# Memory-Buffer.net
KiCad netlist of a schematic drawn in Altium Designer
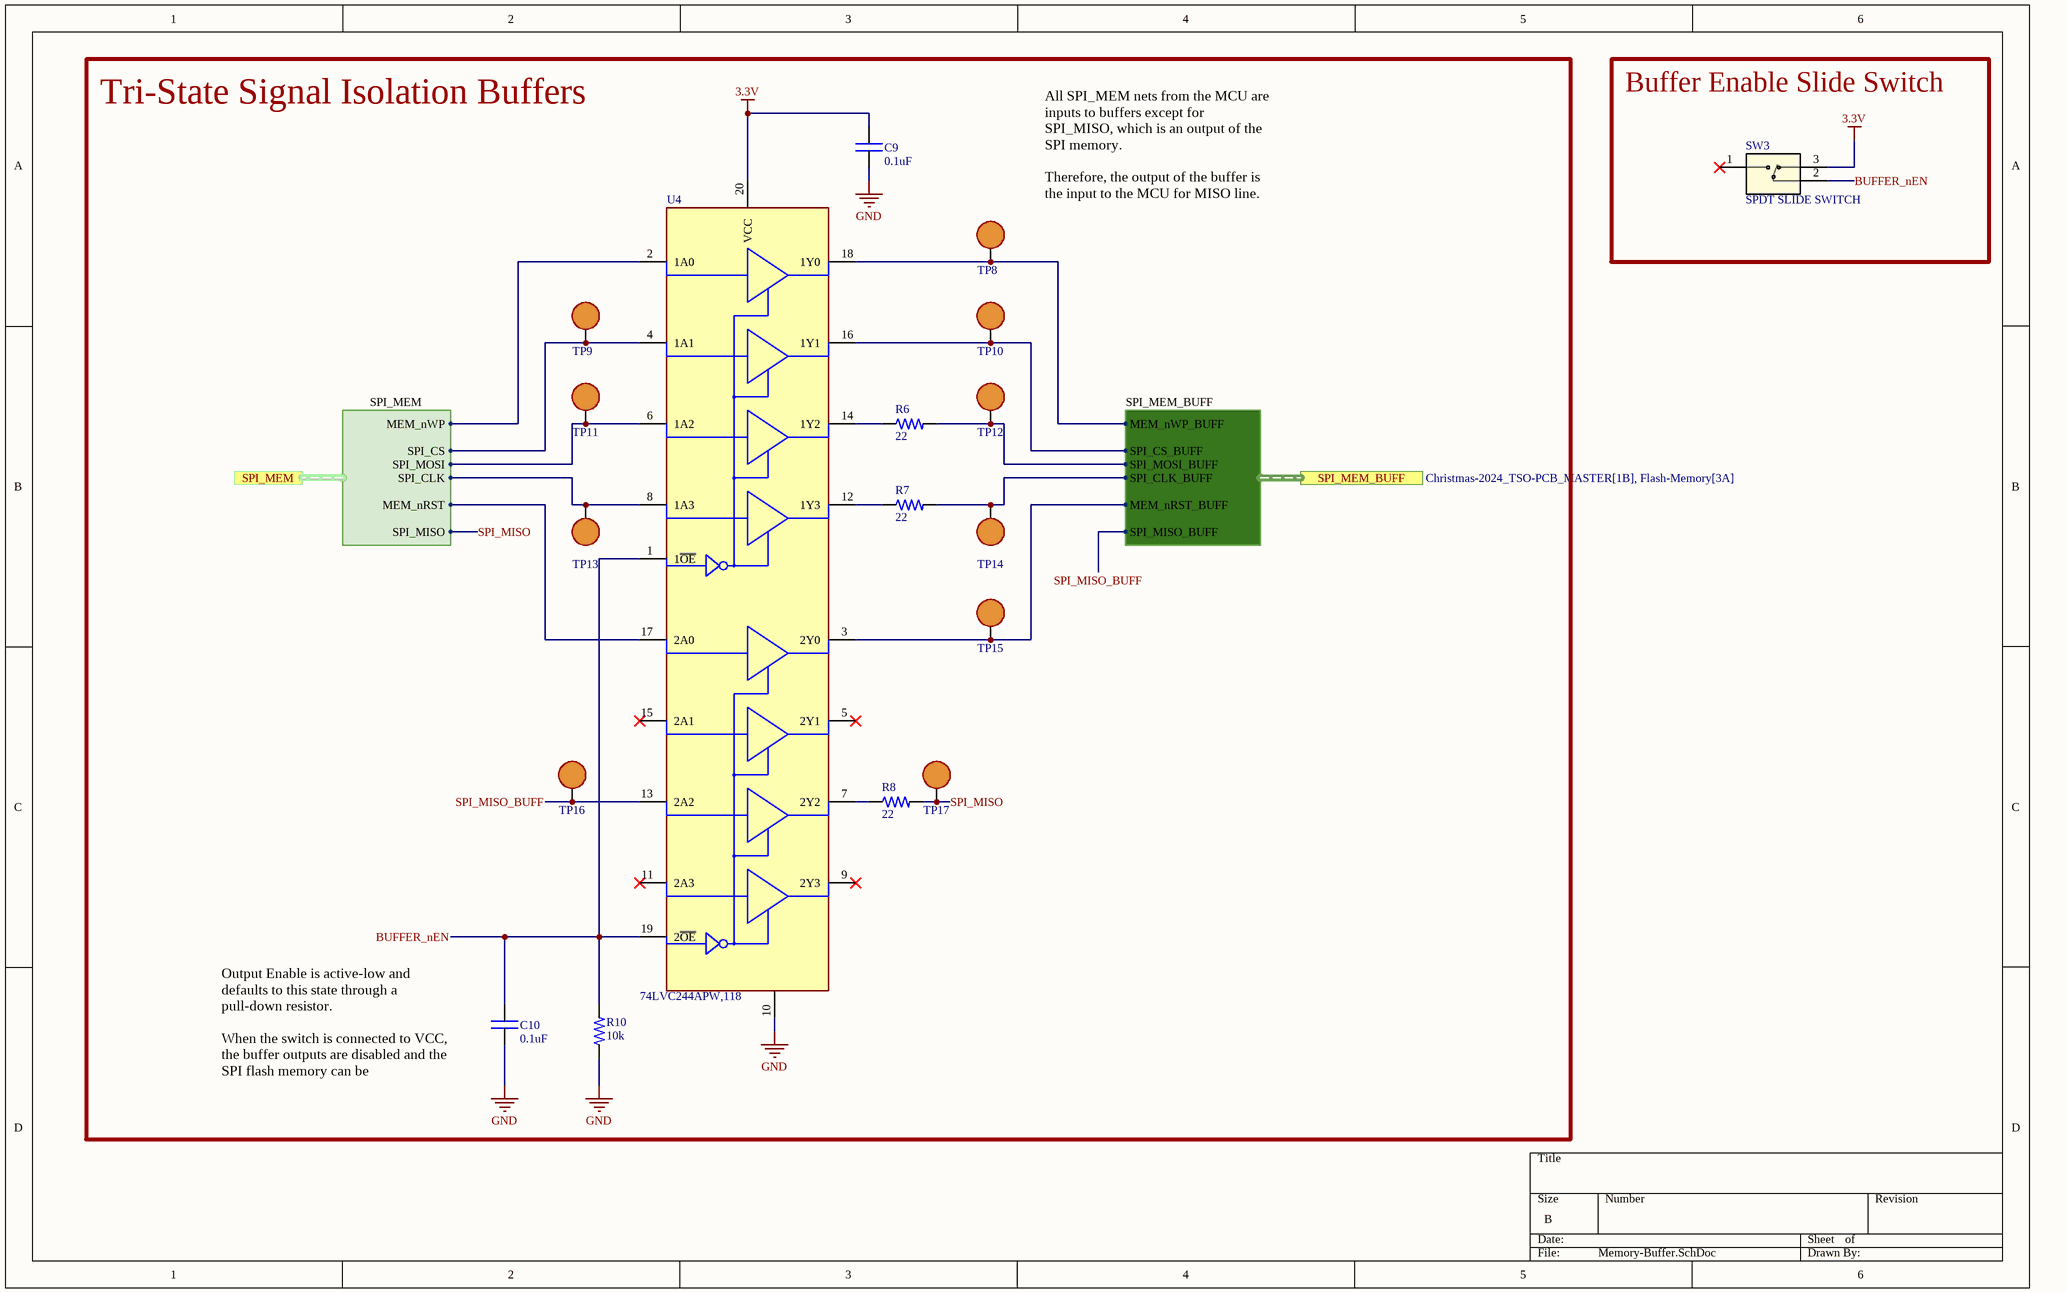
[diagram p0: Memory-Buffer.SchDoc]

(export (version "E")
  (design (tool "Eeschema 10.0.6"))
  (components
    (comp (ref "C9")
      (value "0.1uF")
      (footprint "Christmas-2024_TSO-PCB:0402C")
      (description "Capacitor")
      (fields (field (name "MFR") "Samsung") (field (name "Comment") "CAP"))
      (libsource (lib "Christmas-2024_TSO-PCB") (part "CAP"))
    )
    (comp (ref "C10")
      (value "0.1uF")
      (footprint "Christmas-2024_TSO-PCB:0402C")
      (description "Capacitor")
      (fields (field (name "MFR") "Samsung") (field (name "Comment") "CAP"))
      (libsource (lib "Christmas-2024_TSO-PCB") (part "CAP"))
    )
    (comp (ref "R6")
      (value "22")
      (footprint "Christmas-2024_TSO-PCB:0402R")
      (description "Resistor")
      (fields (field (name "MFR") "YAGEO") (field (name "Comment") "RES"))
      (libsource (lib "Christmas-2024_TSO-PCB") (part "RES"))
    )
    (comp (ref "R7")
      (value "22")
      (footprint "Christmas-2024_TSO-PCB:0402R")
      (description "Resistor")
      (fields (field (name "MFR") "YAGEO") (field (name "Comment") "RES"))
      (libsource (lib "Christmas-2024_TSO-PCB") (part "RES"))
    )
    (comp (ref "R8")
      (value "22")
      (footprint "Christmas-2024_TSO-PCB:0402R")
      (description "Resistor")
      (fields (field (name "MFR") "YAGEO") (field (name "Comment") "RES"))
      (libsource (lib "Christmas-2024_TSO-PCB") (part "RES"))
    )
    (comp (ref "R10")
      (value "10k")
      (footprint "Christmas-2024_TSO-PCB:0402R")
      (description "Resistor")
      (fields (field (name "MFR") "YAGEO") (field (name "Comment") "RES"))
      (libsource (lib "Christmas-2024_TSO-PCB") (part "RES"))
    )
    (comp (ref "SW3")
      (value "SPDT SLIDE SWITCH")
      (footprint "Christmas-2024_TSO-PCB:CJS-1200TB")
      (fields (field (name "MFR") "Nidec Components Corporation"))
      (libsource (lib "Christmas-2024_TSO-PCB") (part "SPDT SLIDE SWITCH"))
    )
    (comp (ref "TP8")
      (value "RCWCTE")
      (footprint "Christmas-2024_TSO-PCB:TP - SMALL")
      (description "Test Point, Surface Mount")
      (libsource (lib "Christmas-2024_TSO-PCB") (part "TEST POINT"))
    )
    (comp (ref "TP9")
      (value "RCWCTE")
      (footprint "Christmas-2024_TSO-PCB:TP - SMALL")
      (description "Test Point, Surface Mount")
      (libsource (lib "Christmas-2024_TSO-PCB") (part "TEST POINT"))
    )
    (comp (ref "TP10")
      (value "RCWCTE")
      (footprint "Christmas-2024_TSO-PCB:TP - SMALL")
      (description "Test Point, Surface Mount")
      (libsource (lib "Christmas-2024_TSO-PCB") (part "TEST POINT"))
    )
    (comp (ref "TP11")
      (value "RCWCTE")
      (footprint "Christmas-2024_TSO-PCB:TP - SMALL")
      (description "Test Point, Surface Mount")
      (libsource (lib "Christmas-2024_TSO-PCB") (part "TEST POINT"))
    )
    (comp (ref "TP12")
      (value "RCWCTE")
      (footprint "Christmas-2024_TSO-PCB:TP - SMALL")
      (description "Test Point, Surface Mount")
      (libsource (lib "Christmas-2024_TSO-PCB") (part "TEST POINT"))
    )
    (comp (ref "TP13")
      (value "RCWCTE")
      (footprint "Christmas-2024_TSO-PCB:TP - SMALL")
      (description "Test Point, Surface Mount")
      (libsource (lib "Christmas-2024_TSO-PCB") (part "TEST POINT"))
    )
    (comp (ref "TP14")
      (value "RCWCTE")
      (footprint "Christmas-2024_TSO-PCB:TP - SMALL")
      (description "Test Point, Surface Mount")
      (libsource (lib "Christmas-2024_TSO-PCB") (part "TEST POINT"))
    )
    (comp (ref "TP15")
      (value "RCWCTE")
      (footprint "Christmas-2024_TSO-PCB:TP - SMALL")
      (description "Test Point, Surface Mount")
      (libsource (lib "Christmas-2024_TSO-PCB") (part "TEST POINT"))
    )
    (comp (ref "TP16")
      (value "RCWCTE")
      (footprint "Christmas-2024_TSO-PCB:TP - SMALL")
      (description "Test Point, Surface Mount")
      (libsource (lib "Christmas-2024_TSO-PCB") (part "TEST POINT"))
    )
    (comp (ref "TP17")
      (value "RCWCTE")
      (footprint "Christmas-2024_TSO-PCB:TP - SMALL")
      (description "Test Point, Surface Mount")
      (libsource (lib "Christmas-2024_TSO-PCB") (part "TEST POINT"))
    )
    (comp (ref "U4")
      (value "74LVC244APW,118")
      (footprint "Christmas-2024_TSO-PCB:20-TSSOP")
      (description "NXP 74LVC244APW,115 Octal Buffer & Line Driver, 3-State, 1.2  3.6 V, 20-Pin TSSOP")
      (fields (field (name "MFR") "Nexperia"))
      (libsource (lib "Christmas-2024_TSO-PCB") (part "TRI-STATE BUFFERS 8 CIRC"))
    )
  )
  (nets
    (net (code "3") (name "/BUFFER_nEN") (class "Default")
      (node (ref "C10") (pin "2") (pinfunction "2_2") (pintype "passive"))
      (node (ref "R10") (pin "2") (pinfunction "2_2") (pintype "passive"))
      (node (ref "SW3") (pin "2") (pinfunction "2_2") (pintype "passive"))
      (node (ref "U4") (pin "1") (pinfunction "1~{OE}_1") (pintype "passive"))
      (node (ref "U4") (pin "19") (pinfunction "2~{OE}_19") (pintype "passive"))
    )
    (net (code "4") (name "/MEM_nRST") (class "Default")
      (node (ref "U4") (pin "17") (pinfunction "2A0_17") (pintype "passive"))
    )
    (net (code "5") (name "/MEM_nRST_BUFF") (class "Default")
      (node (ref "TP15") (pin "1") (pinfunction "0_1") (pintype "passive"))
      (node (ref "U4") (pin "3") (pinfunction "2Y0_3") (pintype "passive"))
    )
    (net (code "6") (name "/MEM_nWP") (class "Default")
      (node (ref "U4") (pin "2") (pinfunction "1A0_2") (pintype "passive"))
    )
    (net (code "7") (name "/MEM_nWP_BUFF") (class "Default")
      (node (ref "TP8") (pin "1") (pinfunction "0_1") (pintype "passive"))
      (node (ref "U4") (pin "18") (pinfunction "1Y0_18") (pintype "passive"))
    )
    (net (code "8") (name "/SPI_CLK") (class "Default")
      (node (ref "TP13") (pin "1") (pinfunction "0_1") (pintype "passive"))
      (node (ref "U4") (pin "8") (pinfunction "1A3_8") (pintype "passive"))
    )
    (net (code "9") (name "/SPI_CLK_BUFF") (class "Default")
      (node (ref "R7") (pin "2") (pinfunction "2_2") (pintype "passive"))
      (node (ref "TP14") (pin "1") (pinfunction "0_1") (pintype "passive"))
    )
    (net (code "10") (name "/SPI_CS") (class "Default")
      (node (ref "TP9") (pin "1") (pinfunction "0_1") (pintype "passive"))
      (node (ref "U4") (pin "4") (pinfunction "1A1_4") (pintype "passive"))
    )
    (net (code "11") (name "/SPI_CS_BUFF") (class "Default")
      (node (ref "TP10") (pin "1") (pinfunction "0_1") (pintype "passive"))
      (node (ref "U4") (pin "16") (pinfunction "1Y1_16") (pintype "passive"))
    )
    (net (code "12") (name "/SPI_MISO") (class "Default")
      (node (ref "R8") (pin "2") (pinfunction "2_2") (pintype "passive"))
      (node (ref "TP17") (pin "1") (pinfunction "0_1") (pintype "passive"))
    )
    (net (code "13") (name "/SPI_MISO_BUFF") (class "Default")
      (node (ref "TP16") (pin "1") (pinfunction "0_1") (pintype "passive"))
      (node (ref "U4") (pin "13") (pinfunction "2A2_13") (pintype "passive"))
    )
    (net (code "14") (name "/SPI_MOSI") (class "Default")
      (node (ref "TP11") (pin "1") (pinfunction "0_1") (pintype "passive"))
      (node (ref "U4") (pin "6") (pinfunction "1A2_6") (pintype "passive"))
    )
    (net (code "15") (name "/SPI_MOSI_BUFF") (class "Default")
      (node (ref "R6") (pin "2") (pinfunction "2_2") (pintype "passive"))
      (node (ref "TP12") (pin "1") (pinfunction "0_1") (pintype "passive"))
    )
    (net (code "18") (name "3.3V") (class "Default")
      (node (ref "C9") (pin "2") (pinfunction "2_2") (pintype "passive"))
      (node (ref "SW3") (pin "3") (pinfunction "3_3") (pintype "passive"))
      (node (ref "U4") (pin "20") (pinfunction "VCC_20") (pintype "passive"))
    )
    (net (code "19") (name "GND") (class "Default")
      (node (ref "C10") (pin "1") (pinfunction "1_1") (pintype "passive"))
      (node (ref "C9") (pin "1") (pinfunction "1_1") (pintype "passive"))
      (node (ref "R10") (pin "1") (pinfunction "1_1") (pintype "passive"))
      (node (ref "U4") (pin "10") (pinfunction "GND_10") (pintype "passive"))
    )
    (net (code "20") (name "Net-(U4-1Y2)") (class "Default")
      (node (ref "R6") (pin "1") (pinfunction "1_1") (pintype "passive"))
      (node (ref "U4") (pin "14") (pinfunction "1Y2_14") (pintype "passive"))
    )
    (net (code "21") (name "Net-(U4-1Y3)") (class "Default")
      (node (ref "R7") (pin "1") (pinfunction "1_1") (pintype "passive"))
      (node (ref "U4") (pin "12") (pinfunction "1Y3_12") (pintype "passive"))
    )
    (net (code "22") (name "Net-(U4-2Y2)") (class "Default")
      (node (ref "R8") (pin "1") (pinfunction "1_1") (pintype "passive"))
      (node (ref "U4") (pin "7") (pinfunction "2Y2_7") (pintype "passive"))
    )
    (net (code "23") (name "unconnected-(SW3-Pad1)") (class "Default")
      (node (ref "SW3") (pin "1") (pinfunction "1_1") (pintype "passive+no_connect"))
    )
    (net (code "24") (name "unconnected-(U4-2A1-Pad15)") (class "Default")
      (node (ref "U4") (pin "15") (pinfunction "2A1_15") (pintype "passive+no_connect"))
    )
    (net (code "25") (name "unconnected-(U4-2A3-Pad11)") (class "Default")
      (node (ref "U4") (pin "11") (pinfunction "2A3_11") (pintype "passive+no_connect"))
    )
    (net (code "26") (name "unconnected-(U4-2Y1-Pad5)") (class "Default")
      (node (ref "U4") (pin "5") (pinfunction "2Y1_5") (pintype "passive+no_connect"))
    )
    (net (code "27") (name "unconnected-(U4-2Y3-Pad9)") (class "Default")
      (node (ref "U4") (pin "9") (pinfunction "2Y3_9") (pintype "passive+no_connect"))
    )
  )
)
